# can.net
KiCad netlist of a schematic drawn in Altium Designer
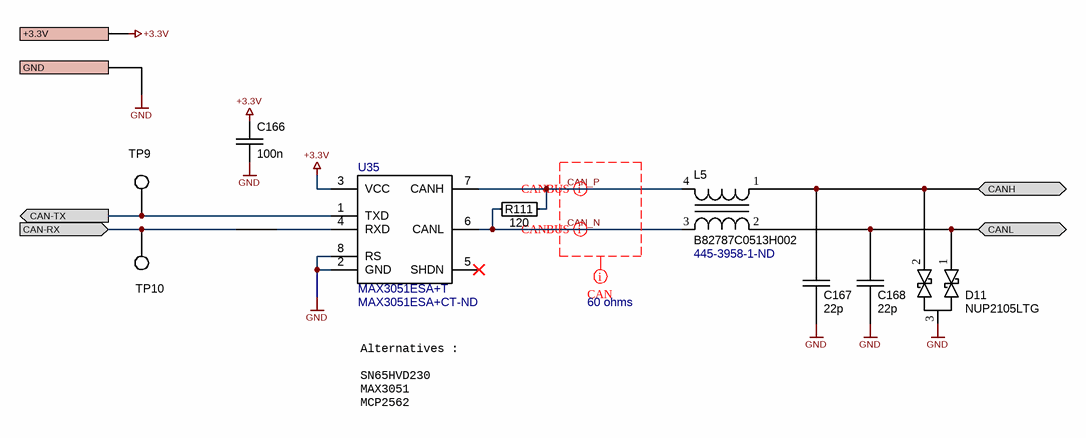
[diagram p0: can.SchDoc]

(export (version "E")
  (design (tool "Eeschema 10.0.6"))
  (components
    (comp (ref "C166")
      (value "100n")
      (footprint "SM/C0402")
      (description "Chip Capacitor")
      (fields (field (name "VOLTAGE") "16V") (field (name "Comment") "CL05A104KP5NNNC"))
      (libsource (lib "kalios") (part "C"))
    )
    (comp (ref "C167")
      (value "22p")
      (footprint "SM/C0402")
      (description "22 pF ±2% 50V Ceramic Capacitor C0G, NP0 0402 (1005 Metric)")
      (fields (field (name "VOLTAGE") "50V"))
      (libsource (lib "kalios") (part "C"))
    )
    (comp (ref "C168")
      (value "22p")
      (footprint "SM/C0402")
      (description "22 pF ±2% 50V Ceramic Capacitor C0G, NP0 0402 (1005 Metric)")
      (fields (field (name "VOLTAGE") "50V"))
      (libsource (lib "kalios") (part "C"))
    )
    (comp (ref "D11")
      (value "NUP2105LTG")
      (footprint "SOT23-3")
      (libsource (lib "kalios") (part "NUP2105LTG"))
    )
    (comp (ref "L5")
      (value "B82787C0513H002")
      (footprint "ACT45B")
      (description "CMC 51UH 200MA 2LN SMD AEC-Q200")
      (fields (field (name "SUPPLIER PART NUMBER 1") "445-3958-1-ND"))
      (libsource (lib "kalios") (part "L_B82787C0513H002"))
    )
    (comp (ref "R111")
      (value "120")
      (footprint "SM/R0402")
      (description "Chip Resistor SMD")
      (libsource (lib "kalios") (part "R"))
    )
    (comp (ref "TP9")
      (value "RCUCTE")
      (footprint "TP/RCUCT")
      (description "PC Test Point Plating Surface Mount Mounting Type")
      (libsource (lib "kalios") (part "TP"))
    )
    (comp (ref "TP10")
      (value "RCUCTE")
      (footprint "TP/RCUCT")
      (description "PC Test Point Plating Surface Mount Mounting Type")
      (libsource (lib "kalios") (part "TP"))
    )
    (comp (ref "U35")
      (value "MAX3051ESA+T")
      (footprint "SOIC8")
      (description "1/1 Transceiver Half CANbus 8-SOIC")
      (fields (field (name "SUPPLIER PART NUMBER 1") "MAX3051ESA+CT-ND"))
      (libsource (lib "kalios") (part "MAX3051"))
    )
  )
  (nets
    (net (code "1") (name "+3.3V") (class "Default")
      (node (ref "C166") (pin "1") (pintype "passive"))
      (node (ref "U35") (pin "3") (pinfunction "VCC_3") (pintype "passive"))
    )
    (net (code "2") (name "/CAN-RX") (class "Default")
      (node (ref "TP10") (pin "1") (pinfunction "1_1") (pintype "passive"))
      (node (ref "U35") (pin "4") (pinfunction "RXD_4") (pintype "passive"))
    )
    (net (code "3") (name "/CAN-TX") (class "Default")
      (node (ref "TP9") (pin "1") (pinfunction "1_1") (pintype "passive"))
      (node (ref "U35") (pin "1") (pinfunction "TXD_1") (pintype "passive"))
    )
    (net (code "4") (name "/CANH") (class "Default")
      (node (ref "C167") (pin "1") (pintype "passive"))
      (node (ref "D11") (pin "2") (pinfunction "21_2") (pintype "passive"))
      (node (ref "L5") (pin "1") (pinfunction "1_1") (pintype "passive"))
    )
    (net (code "5") (name "/CANL") (class "Default")
      (node (ref "C168") (pin "1") (pintype "passive"))
      (node (ref "D11") (pin "1") (pinfunction "1_1") (pintype "passive"))
      (node (ref "L5") (pin "2") (pinfunction "2_2") (pintype "passive"))
    )
    (net (code "6") (name "/CAN_N") (class "Default")
      (node (ref "L5") (pin "3") (pintype "passive"))
      (node (ref "R111") (pin "1") (pintype "passive"))
      (node (ref "U35") (pin "6") (pinfunction "CANL_6") (pintype "passive"))
    )
    (net (code "7") (name "/CAN_P") (class "Default")
      (node (ref "L5") (pin "4") (pintype "passive"))
      (node (ref "R111") (pin "2") (pintype "passive"))
      (node (ref "U35") (pin "7") (pinfunction "CANH_7") (pintype "passive"))
    )
    (net (code "8") (name "GND") (class "Default")
      (node (ref "C166") (pin "2") (pintype "passive"))
      (node (ref "C167") (pin "2") (pintype "passive"))
      (node (ref "C168") (pin "2") (pintype "passive"))
      (node (ref "D11") (pin "3") (pinfunction "3_3") (pintype "passive"))
      (node (ref "U35") (pin "2") (pinfunction "GND_2") (pintype "passive"))
      (node (ref "U35") (pin "8") (pinfunction "RS_8") (pintype "passive"))
    )
    (net (code "9") (name "unconnected-(U35-SHDN-Pad5)") (class "Default")
      (node (ref "U35") (pin "5") (pinfunction "SHDN_5") (pintype "passive+no_connect"))
    )
  )
)
